# arduino_uno_pcb__with_lcd.net
KiCad netlist of a schematic drawn in EAGLE
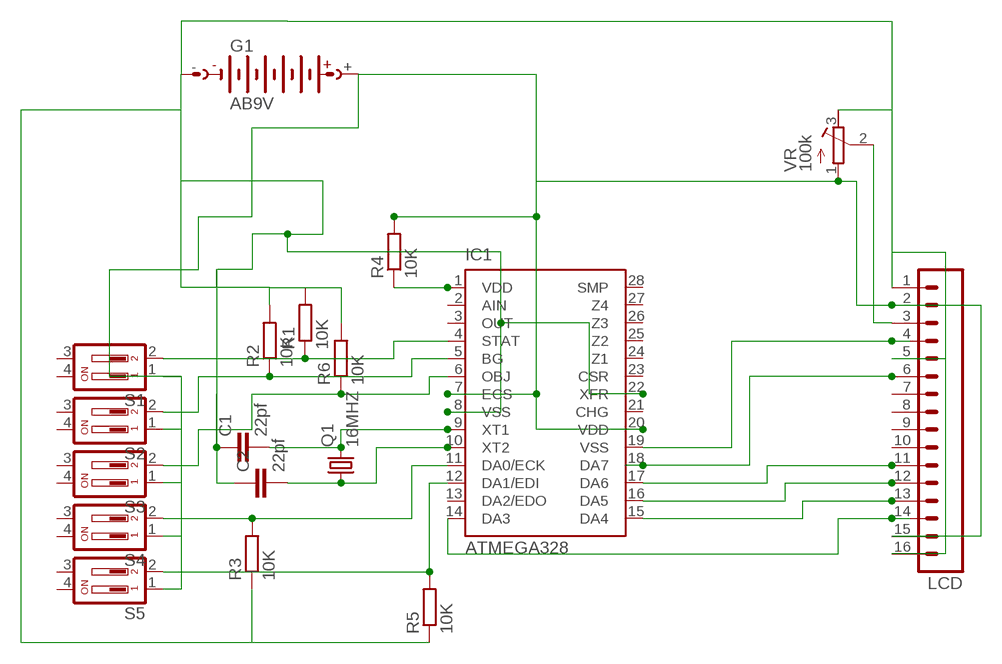
[diagram p0: schematic, sheet 1]

(export (version "E")
  (design (tool "Eeschema 10.0.6"))
  (components
    (comp (ref "C1")
      (value "22pf")
      (footprint "eagle-import:C2.5-2")
      (libsource (lib "eagle-import") (part "C2.5/2"))
    )
    (comp (ref "C2")
      (value "22pf")
      (footprint "eagle-import:C2.5-2")
      (libsource (lib "eagle-import") (part "C2.5/2"))
    )
    (comp (ref "G1")
      (value "AB9V")
      (footprint "eagle-import:AB9V")
      (libsource (lib "eagle-import") (part "AB9V"))
    )
    (comp (ref "IC1")
      (value "ATMEGA328")
      (footprint "eagle-import:DIL28-3")
      (libsource (lib "eagle-import") (part "QT9701BD"))
    )
    (comp (ref "LCD")
      (value "M16")
      (footprint "eagle-import:16P")
      (libsource (lib "eagle-import") (part "M16"))
    )
    (comp (ref "Q1")
      (value "16MHZ")
      (footprint "eagle-import:HC49_S")
      (libsource (lib "eagle-import") (part "CRYSTALHC49S"))
    )
    (comp (ref "R1")
      (value "10K")
      (footprint "eagle-import:0207_10")
      (libsource (lib "eagle-import") (part "R-EU_0207/10"))
    )
    (comp (ref "R2")
      (value "10K")
      (footprint "eagle-import:0207_10")
      (libsource (lib "eagle-import") (part "R-EU_0207/10"))
    )
    (comp (ref "R3")
      (value "10K")
      (footprint "eagle-import:0207_10")
      (libsource (lib "eagle-import") (part "R-EU_0207/10"))
    )
    (comp (ref "R4")
      (value "10K")
      (footprint "eagle-import:0207_10")
      (libsource (lib "eagle-import") (part "R-EU_0207/10"))
    )
    (comp (ref "R5")
      (value "10K")
      (footprint "eagle-import:0207_10")
      (libsource (lib "eagle-import") (part "R-EU_0207/10"))
    )
    (comp (ref "R6")
      (value "10K")
      (footprint "eagle-import:0207_10")
      (libsource (lib "eagle-import") (part "R-EU_0207/10"))
    )
    (comp (ref "S1")
      (value "DP02")
      (footprint "eagle-import:DP-02")
      (fields (field (name "MPN") "MCDP02"))
      (libsource (lib "eagle-import") (part "DP02"))
    )
    (comp (ref "S2")
      (value "DP02")
      (footprint "eagle-import:DP-02")
      (fields
        (field (name "MPN") "MCDP02")
        (field (name "MPN_1") "MCDP02")
        (field (name "OC_FARNELL") "1255233")
        (field (name "OC_NEWARK") "26M1095")
      )
      (libsource (lib "eagle-import") (part "DP02"))
    )
    (comp (ref "S3")
      (value "DP02")
      (footprint "eagle-import:DP-02")
      (fields
        (field (name "MPN") "MCDP02")
        (field (name "MPN_1") "MCDP02")
        (field (name "OC_FARNELL") "1255233")
        (field (name "OC_NEWARK") "26M1095")
      )
      (libsource (lib "eagle-import") (part "DP02"))
    )
    (comp (ref "S4")
      (value "DP02")
      (footprint "eagle-import:DP-02")
      (fields
        (field (name "MPN") "MCDP02")
        (field (name "MPN_1") "MCDP02")
        (field (name "OC_FARNELL") "1255233")
        (field (name "OC_NEWARK") "26M1095")
      )
      (libsource (lib "eagle-import") (part "DP02"))
    )
    (comp (ref "S5")
      (value "DP02")
      (footprint "eagle-import:DP-02")
      (fields
        (field (name "MPN") "MCDP02")
        (field (name "MPN_1") "MCDP02")
        (field (name "OC_FARNELL") "1255233")
        (field (name "OC_NEWARK") "26M1095")
      )
      (libsource (lib "eagle-import") (part "DP02"))
    )
    (comp (ref "VR")
      (value "100k")
      (footprint "eagle-import:RTRIM64P")
      (libsource (lib "eagle-import") (part "R-TRIMM64P"))
    )
  )
  (nets
    (net (code "1") (name "Net-(IC1-BG)") (class "Default")
      (node (ref "IC1") (pin "5") (pinfunction "BG_5") (pintype "input"))
      (node (ref "R2") (pin "1") (pinfunction "1_1") (pintype "passive"))
      (node (ref "S2") (pin "2") (pinfunction "2_2") (pintype "passive"))
    )
    (net (code "2") (name "Net-(IC1-DA0{slash}ECK)") (class "Default")
      (node (ref "IC1") (pin "11") (pinfunction "DA0/ECK_11") (pintype "output"))
      (node (ref "R3") (pin "2") (pinfunction "2_2") (pintype "passive"))
      (node (ref "S4") (pin "2") (pinfunction "2_2") (pintype "passive"))
    )
    (net (code "3") (name "Net-(IC1-DA1{slash}EDI)") (class "Default")
      (node (ref "IC1") (pin "12") (pinfunction "DA1/EDI_12") (pintype "output"))
      (node (ref "R5") (pin "2") (pinfunction "2_2") (pintype "passive"))
      (node (ref "S5") (pin "2") (pinfunction "2_2") (pintype "passive"))
    )
    (net (code "4") (name "Net-(IC1-DA3)") (class "Default")
      (node (ref "IC1") (pin "14") (pinfunction "DA3_14") (pintype "output"))
      (node (ref "LCD") (pin "14") (pinfunction "14_14") (pintype "passive"))
    )
    (net (code "5") (name "Net-(IC1-DA4)") (class "Default")
      (node (ref "IC1") (pin "15") (pinfunction "DA4_15") (pintype "output"))
      (node (ref "LCD") (pin "13") (pinfunction "13_13") (pintype "passive"))
    )
    (net (code "6") (name "Net-(IC1-DA5)") (class "Default")
      (node (ref "IC1") (pin "16") (pinfunction "DA5_16") (pintype "output"))
      (node (ref "LCD") (pin "12") (pinfunction "12_12") (pintype "passive"))
    )
    (net (code "7") (name "Net-(IC1-DA6)") (class "Default")
      (node (ref "IC1") (pin "17") (pinfunction "DA6_17") (pintype "output"))
      (node (ref "LCD") (pin "11") (pinfunction "11_11") (pintype "passive"))
    )
    (net (code "8") (name "Net-(IC1-DA7)") (class "Default")
      (node (ref "IC1") (pin "18") (pinfunction "DA7_18") (pintype "output"))
      (node (ref "LCD") (pin "6") (pinfunction "6_6") (pintype "passive"))
    )
    (net (code "9") (name "Net-(IC1-ECS)") (class "Default")
      (node (ref "G1") (pin "+") (pinfunction "+_+") (pintype "passive"))
      (node (ref "IC1") (pin "20") (pinfunction "VDD_20") (pintype "input"))
      (node (ref "IC1") (pin "7") (pinfunction "ECS_7") (pintype "output"))
      (node (ref "LCD") (pin "15") (pinfunction "15_15") (pintype "passive"))
      (node (ref "LCD") (pin "2") (pinfunction "2_2") (pintype "passive"))
      (node (ref "R4") (pin "2") (pinfunction "2_2") (pintype "passive"))
      (node (ref "S1") (pin "1") (pinfunction "1_1") (pintype "passive"))
      (node (ref "S2") (pin "1") (pinfunction "1_1") (pintype "passive"))
      (node (ref "S3") (pin "1") (pinfunction "1_1") (pintype "passive"))
      (node (ref "S4") (pin "1") (pinfunction "1_1") (pintype "passive"))
      (node (ref "S5") (pin "1") (pinfunction "1_1") (pintype "passive"))
      (node (ref "VR") (pin "1") (pinfunction "E_1") (pintype "passive"))
    )
    (net (code "10") (name "Net-(IC1-OBJ)") (class "Default")
      (node (ref "IC1") (pin "6") (pinfunction "OBJ_6") (pintype "input"))
      (node (ref "R6") (pin "1") (pinfunction "1_1") (pintype "passive"))
      (node (ref "S3") (pin "2") (pinfunction "2_2") (pintype "passive"))
    )
    (net (code "11") (name "Net-(IC1-STAT)") (class "Default")
      (node (ref "IC1") (pin "4") (pinfunction "STAT_4") (pintype "output"))
      (node (ref "R1") (pin "1") (pinfunction "1_1") (pintype "passive"))
      (node (ref "S1") (pin "2") (pinfunction "2_2") (pintype "passive"))
    )
    (net (code "12") (name "Net-(IC1-VDD-Pad1)") (class "Default")
      (node (ref "IC1") (pin "1") (pinfunction "VDD_1") (pintype "input"))
      (node (ref "R4") (pin "1") (pinfunction "1_1") (pintype "passive"))
    )
    (net (code "13") (name "Net-(IC1-VSS-Pad19)") (class "Default")
      (node (ref "IC1") (pin "19") (pinfunction "VSS_19") (pintype "input"))
      (node (ref "LCD") (pin "4") (pinfunction "4_4") (pintype "passive"))
    )
    (net (code "14") (name "Net-(IC1-XFR)") (class "Default")
      (node (ref "C1") (pin "1") (pinfunction "1_1") (pintype "passive"))
      (node (ref "C2") (pin "1") (pinfunction "1_1") (pintype "passive"))
      (node (ref "G1") (pin "-") (pinfunction "-_-") (pintype "passive"))
      (node (ref "IC1") (pin "22") (pinfunction "XFR_22") (pintype "output"))
      (node (ref "IC1") (pin "8") (pinfunction "VSS_8") (pintype "input"))
      (node (ref "LCD") (pin "1") (pinfunction "1_1") (pintype "passive"))
      (node (ref "LCD") (pin "16") (pinfunction "16_16") (pintype "passive"))
      (node (ref "LCD") (pin "5") (pinfunction "5_5") (pintype "passive"))
      (node (ref "R1") (pin "2") (pinfunction "2_2") (pintype "passive"))
      (node (ref "R2") (pin "2") (pinfunction "2_2") (pintype "passive"))
      (node (ref "R3") (pin "1") (pinfunction "1_1") (pintype "passive"))
      (node (ref "R5") (pin "1") (pinfunction "1_1") (pintype "passive"))
      (node (ref "R6") (pin "2") (pinfunction "2_2") (pintype "passive"))
      (node (ref "VR") (pin "3") (pinfunction "A_3") (pintype "passive"))
    )
    (net (code "15") (name "Net-(IC1-XT1)") (class "Default")
      (node (ref "C1") (pin "2") (pinfunction "2_2") (pintype "passive"))
      (node (ref "IC1") (pin "9") (pinfunction "XT1_9") (pintype "input"))
      (node (ref "Q1") (pin "2") (pinfunction "2_2") (pintype "passive"))
    )
    (net (code "16") (name "Net-(IC1-XT2)") (class "Default")
      (node (ref "C2") (pin "2") (pinfunction "2_2") (pintype "passive"))
      (node (ref "IC1") (pin "10") (pinfunction "XT2_10") (pintype "output"))
      (node (ref "Q1") (pin "1") (pinfunction "1_1") (pintype "passive"))
    )
    (net (code "17") (name "Net-(VR-S)") (class "Default")
      (node (ref "LCD") (pin "3") (pinfunction "3_3") (pintype "passive"))
      (node (ref "VR") (pin "2") (pinfunction "S_2") (pintype "passive"))
    )
    (net (code "18") (name "unconnected-(IC1-AIN-Pad2)") (class "Default")
      (node (ref "IC1") (pin "2") (pinfunction "AIN_2") (pintype "input"))
    )
    (net (code "19") (name "unconnected-(IC1-CHG-Pad21)") (class "Default")
      (node (ref "IC1") (pin "21") (pinfunction "CHG_21") (pintype "output"))
    )
    (net (code "20") (name "unconnected-(IC1-CSR-Pad23)") (class "Default")
      (node (ref "IC1") (pin "23") (pinfunction "CSR_23") (pintype "output"))
    )
    (net (code "21") (name "unconnected-(IC1-DA2{slash}EDO-Pad13)") (class "Default")
      (node (ref "IC1") (pin "13") (pinfunction "DA2/EDO_13") (pintype "output"))
    )
    (net (code "22") (name "unconnected-(IC1-OUT-Pad3)") (class "Default")
      (node (ref "IC1") (pin "3") (pinfunction "OUT_3") (pintype "output"))
    )
    (net (code "23") (name "unconnected-(IC1-SMP-Pad28)") (class "Default")
      (node (ref "IC1") (pin "28") (pinfunction "SMP_28") (pintype "output"))
    )
    (net (code "24") (name "unconnected-(IC1-Z1-Pad24)") (class "Default")
      (node (ref "IC1") (pin "24") (pinfunction "Z1_24") (pintype "output"))
    )
    (net (code "25") (name "unconnected-(IC1-Z2-Pad25)") (class "Default")
      (node (ref "IC1") (pin "25") (pinfunction "Z2_25") (pintype "output"))
    )
    (net (code "26") (name "unconnected-(IC1-Z3-Pad26)") (class "Default")
      (node (ref "IC1") (pin "26") (pinfunction "Z3_26") (pintype "output"))
    )
    (net (code "27") (name "unconnected-(IC1-Z4-Pad27)") (class "Default")
      (node (ref "IC1") (pin "27") (pinfunction "Z4_27") (pintype "output"))
    )
    (net (code "28") (name "unconnected-(LCD-Pad7)") (class "Default")
      (node (ref "LCD") (pin "7") (pinfunction "7_7") (pintype "passive"))
    )
    (net (code "29") (name "unconnected-(LCD-Pad8)") (class "Default")
      (node (ref "LCD") (pin "8") (pinfunction "8_8") (pintype "passive"))
    )
    (net (code "30") (name "unconnected-(LCD-Pad9)") (class "Default")
      (node (ref "LCD") (pin "9") (pinfunction "9_9") (pintype "passive"))
    )
    (net (code "31") (name "unconnected-(LCD-Pad10)") (class "Default")
      (node (ref "LCD") (pin "10") (pinfunction "10_10") (pintype "passive"))
    )
    (net (code "32") (name "unconnected-(S1-Pad3)") (class "Default")
      (node (ref "S1") (pin "3") (pinfunction "3_3") (pintype "passive"))
    )
    (net (code "33") (name "unconnected-(S1-Pad4)") (class "Default")
      (node (ref "S1") (pin "4") (pinfunction "4_4") (pintype "passive"))
    )
    (net (code "34") (name "unconnected-(S2-Pad3)") (class "Default")
      (node (ref "S2") (pin "3") (pinfunction "3_3") (pintype "passive"))
    )
    (net (code "35") (name "unconnected-(S2-Pad4)") (class "Default")
      (node (ref "S2") (pin "4") (pinfunction "4_4") (pintype "passive"))
    )
    (net (code "36") (name "unconnected-(S3-Pad3)") (class "Default")
      (node (ref "S3") (pin "3") (pinfunction "3_3") (pintype "passive"))
    )
    (net (code "37") (name "unconnected-(S3-Pad4)") (class "Default")
      (node (ref "S3") (pin "4") (pinfunction "4_4") (pintype "passive"))
    )
    (net (code "38") (name "unconnected-(S4-Pad3)") (class "Default")
      (node (ref "S4") (pin "3") (pinfunction "3_3") (pintype "passive"))
    )
    (net (code "39") (name "unconnected-(S4-Pad4)") (class "Default")
      (node (ref "S4") (pin "4") (pinfunction "4_4") (pintype "passive"))
    )
    (net (code "40") (name "unconnected-(S5-Pad3)") (class "Default")
      (node (ref "S5") (pin "3") (pinfunction "3_3") (pintype "passive"))
    )
    (net (code "41") (name "unconnected-(S5-Pad4)") (class "Default")
      (node (ref "S5") (pin "4") (pinfunction "4_4") (pintype "passive"))
    )
  )
)
